# color_Sensor_Schematic.net
KiCad netlist of a schematic drawn in Altium Designer
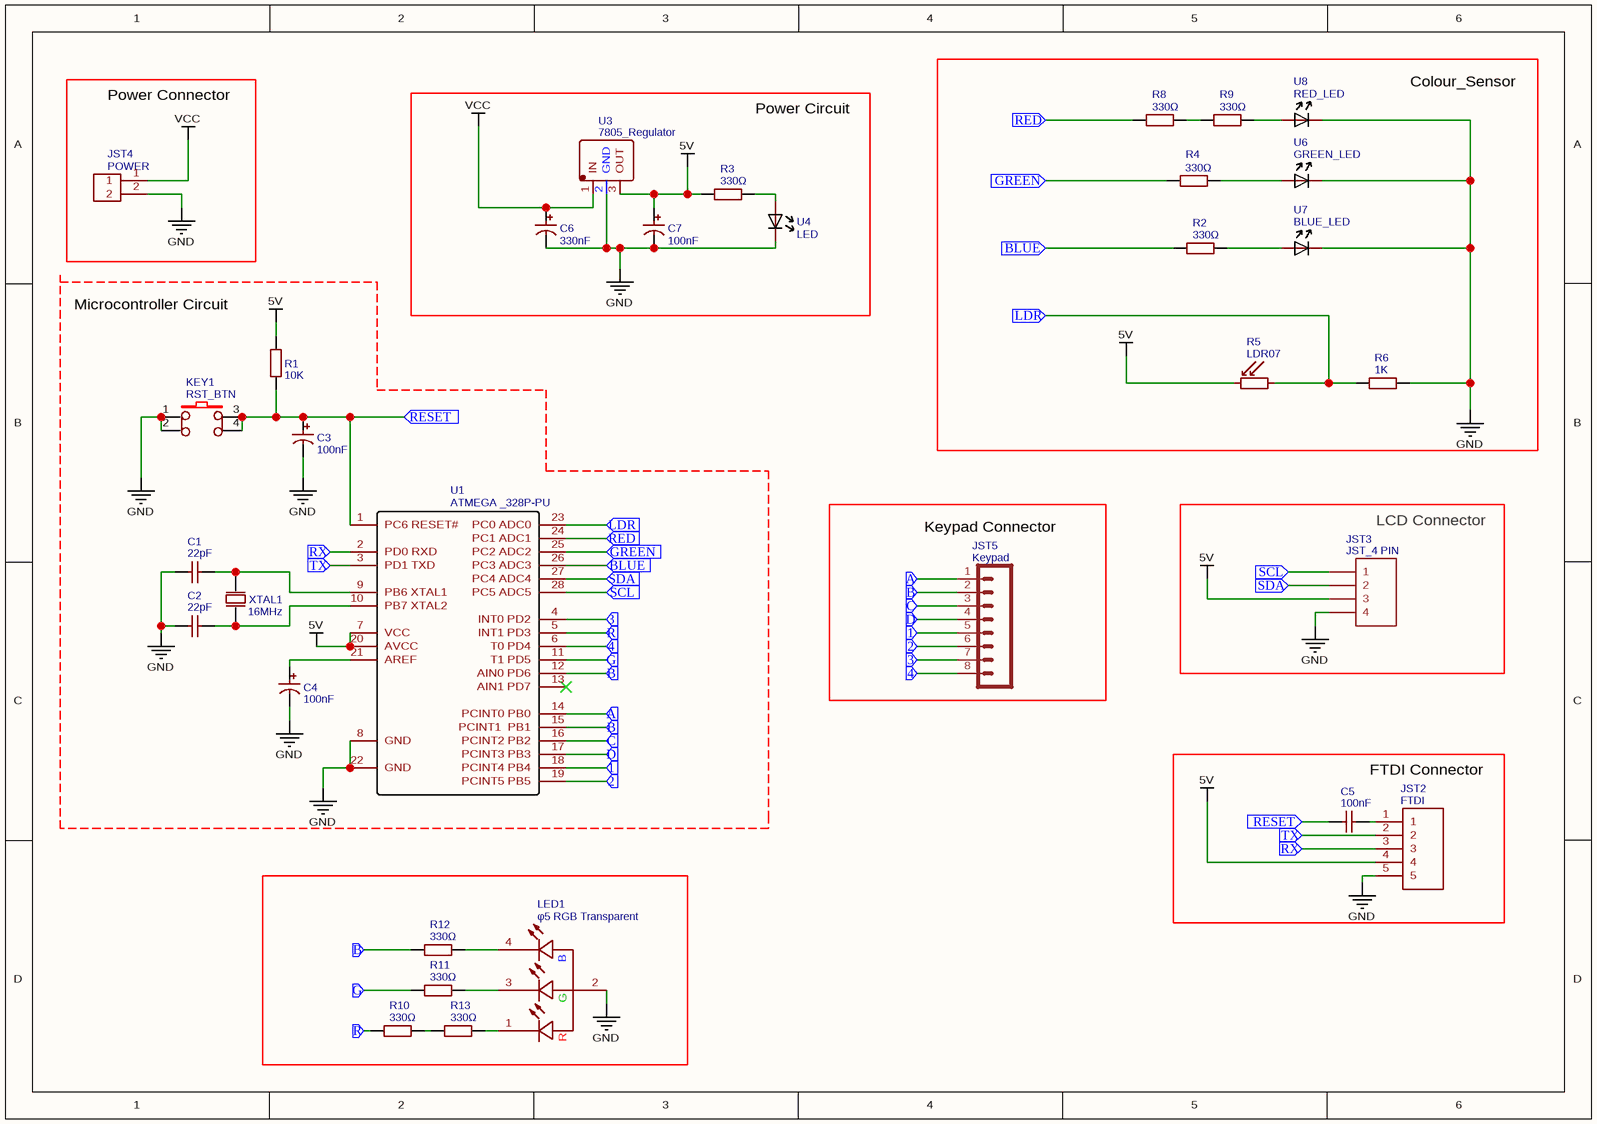
[diagram p0: color Sensor_Schematic.schdoc]

(export (version "E")
  (design (tool "Eeschema 10.0.6"))
  (components
    (comp (ref "C1")
      (value "22pF")
      (fields
        (field (name "BOM_MANUFACTURER PART") "22pf/50V 10%")
        (field (name "BOM_SUPPLIER PART") "C9316")
      )
      (libsource (lib "altium-import") (part "root_0_22pF_"))
    )
    (comp (ref "C2")
      (value "22pF")
      (fields
        (field (name "BOM_MANUFACTURER PART") "22pf/50V 10%")
        (field (name "BOM_SUPPLIER PART") "C9316")
      )
      (libsource (lib "altium-import") (part "root_0_22pF_"))
    )
    (comp (ref "C3")
      (value "100nF")
      (fields (field (name "BOM_MANUFACTURER PART") "0.1UF 50V") (field (name "BOM_SUPPLIER PART") "C28061"))
      (libsource (lib "altium-import") (part "root_0_100nF_"))
    )
    (comp (ref "C4")
      (value "100nF")
      (fields (field (name "BOM_MANUFACTURER PART") "0.1UF 50V") (field (name "BOM_SUPPLIER PART") "C28061"))
      (libsource (lib "altium-import") (part "root_0_100nF_"))
    )
    (comp (ref "C5")
      (value "100nF")
      (fields
        (field (name "BOM_MANUFACTURER PART") "0.1UF(104) +-20% 63v")
        (field (name "BOM_SUPPLIER PART") "C19355")
      )
      (libsource (lib "") (part "root_0_100nF__1"))
    )
    (comp (ref "C6")
      (value "330nF")
      (fields
        (field (name "BOM_MANUFACTURER PART") "0.33uF 50V 5*11")
        (field (name "BOM_SUPPLIER PART") "C45097")
      )
      (libsource (lib "altium-import") (part "root_0_330nF_"))
    )
    (comp (ref "C7")
      (value "100nF")
      (fields (field (name "BOM_MANUFACTURER PART") "0.1UF 50V") (field (name "BOM_SUPPLIER PART") "C28061"))
      (libsource (lib "altium-import") (part "root_0_100nF_"))
    )
    (comp (ref "JST2")
      (value "FTDI")
      (fields (field (name "CONTRIBUTOR") "MagnusInc"))
      (libsource (lib "altium-import") (part "root_3_FTDI_"))
    )
    (comp (ref "JST3")
      (value "JST_4 PIN")
      (fields (field (name "CONTRIBUTOR") "fabiano.riccardi"))
      (libsource (lib "altium-import") (part "root_0_JST_4 PIN_"))
    )
    (comp (ref "JST4")
      (value "POWER")
      (fields
        (field (name "BOM_MANUFACTURER PART") "XHB-2A Connector")
        (field (name "BOM_SUPPLIER PART") "C57981")
      )
      (libsource (lib "altium-import") (part "root_0_POWER_"))
    )
    (comp (ref "JST5")
      (value "Keypad")
      (description "Header 4")
      (fields (field (name "CONTRIBUTOR") "Vlad Tarabega"))
      (libsource (lib "altium-import") (part "root_2_Keypad_"))
    )
    (comp (ref "KEY1")
      (value "RST_BTN")
      (fields
        (field (name "BOM_SUPPLIER PART") "C59980")
        (field (name "BOM_MANUFACTURER PART") "button6*6*8.5")
      )
      (libsource (lib "altium-import") (part "root_0_RST_BTN_"))
    )
    (comp (ref "LED1")
      (value "φ5 RGB Transparent")
      (fields
        (field (name "BOM_MANUFACTURER PART") "φ5 RGB Transparent LED")
        (field (name "BOM_SUPPLIER PART") "C32985")
        (field (name "CONTRIBUTOR") "LCSC")
      )
      (libsource (lib "altium-import") (part "root_3_φ5 RGB Transparent_"))
    )
    (comp (ref "R1")
      (value "10K")
      (fields
        (field (name "POWER") "1/4W")
        (field (name "TOLERANCE") "±1%")
        (field (name "BOM_SUPPLIER PART") "E57439")
      )
      (libsource (lib "altium-import") (part "root_1_10K_"))
    )
    (comp (ref "R2")
      (value "330Ω")
      (fields
        (field (name "POWER") "1/4W")
        (field (name "TOLERANCE") "±1%")
        (field (name "BOM_SUPPLIER PART") "E57439")
      )
      (libsource (lib "altium-import") (part "root_0_330Ω_"))
    )
    (comp (ref "R3")
      (value "330Ω")
      (fields
        (field (name "POWER") "1/4W")
        (field (name "TOLERANCE") "±1%")
        (field (name "BOM_SUPPLIER PART") "E57439")
      )
      (libsource (lib "altium-import") (part "root_0_330Ω_"))
    )
    (comp (ref "R4")
      (value "330Ω")
      (fields
        (field (name "POWER") "1/4W")
        (field (name "TOLERANCE") "±1%")
        (field (name "BOM_SUPPLIER PART") "E57439")
      )
      (libsource (lib "altium-import") (part "root_0_330Ω_"))
    )
    (comp (ref "R5")
      (value "LDR07")
      (fields (field (name "CONTRIBUTOR") "KiCAD"))
      (libsource (lib "altium-import") (part "root_3_LDR07_"))
    )
    (comp (ref "R6")
      (value "1K")
      (fields
        (field (name "POWER") "1/4W")
        (field (name "TOLERANCE") "±1%")
        (field (name "BOM_SUPPLIER PART") "E57439")
      )
      (libsource (lib "altium-import") (part "root_0_1K_"))
    )
    (comp (ref "R8")
      (value "330Ω")
      (fields
        (field (name "POWER") "1/4W")
        (field (name "TOLERANCE") "±1%")
        (field (name "BOM_SUPPLIER PART") "E57439")
      )
      (libsource (lib "altium-import") (part "root_0_330Ω_"))
    )
    (comp (ref "R9")
      (value "330Ω")
      (fields
        (field (name "POWER") "1/4W")
        (field (name "TOLERANCE") "±1%")
        (field (name "BOM_SUPPLIER PART") "E57439")
      )
      (libsource (lib "altium-import") (part "root_0_330Ω_"))
    )
    (comp (ref "R10")
      (value "330Ω")
      (fields
        (field (name "POWER") "1/4W")
        (field (name "TOLERANCE") "±1%")
        (field (name "BOM_SUPPLIER PART") "E57439")
      )
      (libsource (lib "altium-import") (part "root_0_330Ω_"))
    )
    (comp (ref "R11")
      (value "330Ω")
      (fields
        (field (name "POWER") "1/4W")
        (field (name "TOLERANCE") "±1%")
        (field (name "BOM_SUPPLIER PART") "E57439")
      )
      (libsource (lib "altium-import") (part "root_0_330Ω_"))
    )
    (comp (ref "R12")
      (value "330Ω")
      (fields
        (field (name "POWER") "1/4W")
        (field (name "TOLERANCE") "±1%")
        (field (name "BOM_SUPPLIER PART") "E57439")
      )
      (libsource (lib "altium-import") (part "root_0_330Ω_"))
    )
    (comp (ref "R13")
      (value "330Ω")
      (fields
        (field (name "POWER") "1/4W")
        (field (name "TOLERANCE") "±1%")
        (field (name "BOM_SUPPLIER PART") "E57439")
      )
      (libsource (lib "altium-import") (part "root_0_330Ω_"))
    )
    (comp (ref "U1")
      (value "ATMEGA _328P-PU")
      (fields
        (field (name "BOM_MANUFACTURER PART") "ATMEGA328P-PU")
        (field (name "BOM_SUPPLIER PART") "C33901")
        (field (name "CONTRIBUTOR") "LCSC")
      )
      (libsource (lib "altium-import") (part "root_0_ATMEGA _328P-PU_"))
    )
    (comp (ref "U3")
      (value "7805_Regulator")
      (fields
        (field (name "BOM_SUPPLIER PART") "C305416")
        (field (name "BOM_MANUFACTURER PART") "7805")
        (field (name "CONTRIBUTOR") "LCSC")
      )
      (libsource (lib "altium-import") (part "root_1_7805_Regulator_"))
    )
    (comp (ref "U4")
      (value "LED")
      (fields (field (name "BOM_MANUFACTURER PART") "5mm LED") (field (name "CONTRIBUTOR") "Axbri"))
      (libsource (lib "altium-import") (part "root_3_LED_"))
    )
    (comp (ref "U6")
      (value "GREEN_LED")
      (fields (field (name "BOM_MANUFACTURER PART") "5mm LED") (field (name "CONTRIBUTOR") "Axbri"))
      (libsource (lib "altium-import") (part "root_0_GREEN_LED_"))
    )
    (comp (ref "U7")
      (value "BLUE_LED")
      (fields (field (name "BOM_MANUFACTURER PART") "5mm LED") (field (name "CONTRIBUTOR") "Axbri"))
      (libsource (lib "altium-import") (part "root_0_BLUE_LED_"))
    )
    (comp (ref "U8")
      (value "RED_LED")
      (fields (field (name "BOM_MANUFACTURER PART") "5mm LED") (field (name "CONTRIBUTOR") "Axbri"))
      (libsource (lib "altium-import") (part "root_0_RED_LED_"))
    )
    (comp (ref "XTAL1")
      (value "16MHz")
      (fields
        (field (name "BOM_MANUFACTURER PART") "0SC-16MHz")
        (field (name "CONTRIBUTOR") "Mantas Petrauskas")
      )
      (libsource (lib "altium-import") (part "root_1_16MHz_"))
    )
  )
  (nets
    (net (code "1") (name "/1") (class "Default")
      (node (ref "JST5") (pin "5") (pinfunction "5_5") (pintype "passive"))
      (node (ref "U1") (pin "18") (pinfunction "PCINT4_PB4_18") (pintype "passive"))
    )
    (net (code "2") (name "/2") (class "Default")
      (node (ref "JST5") (pin "6") (pinfunction "6_6") (pintype "passive"))
      (node (ref "U1") (pin "19") (pinfunction "PCINT5_PB5_19") (pintype "passive"))
    )
    (net (code "3") (name "/3") (class "Default")
      (node (ref "JST5") (pin "7") (pinfunction "7_7") (pintype "passive"))
      (node (ref "U1") (pin "4") (pinfunction "INT0_PD2_4") (pintype "passive"))
    )
    (net (code "4") (name "/4") (class "Default")
      (node (ref "JST5") (pin "8") (pinfunction "8_8") (pintype "passive"))
      (node (ref "U1") (pin "6") (pinfunction "T0_PD4_6") (pintype "passive"))
    )
    (net (code "5") (name "/A") (class "Default")
      (node (ref "JST5") (pin "1") (pinfunction "1_1") (pintype "passive"))
      (node (ref "U1") (pin "14") (pinfunction "PCINT0_PB0_14") (pintype "passive"))
    )
    (net (code "6") (name "/B") (class "Default")
      (node (ref "JST5") (pin "2") (pinfunction "2_2") (pintype "passive"))
      (node (ref "R12") (pin "1") (pinfunction "1_1") (pintype "passive"))
      (node (ref "U1") (pin "12") (pinfunction "AIN0_PD6_12") (pintype "passive"))
      (node (ref "U1") (pin "15") (pinfunction "PCINT1__PB1_15") (pintype "passive"))
    )
    (net (code "7") (name "/BLUE") (class "Default")
      (node (ref "R2") (pin "1") (pinfunction "1_1") (pintype "passive"))
      (node (ref "U1") (pin "26") (pinfunction "PC3_ADC3_26") (pintype "passive"))
    )
    (net (code "8") (name "/C") (class "Default")
      (node (ref "JST5") (pin "3") (pinfunction "3_3") (pintype "passive"))
      (node (ref "U1") (pin "16") (pinfunction "PCINT2_PB2_16") (pintype "passive"))
    )
    (net (code "9") (name "/D") (class "Default")
      (node (ref "JST5") (pin "4") (pinfunction "4_4") (pintype "passive"))
      (node (ref "U1") (pin "17") (pinfunction "PCINT3_PB3_17") (pintype "passive"))
    )
    (net (code "10") (name "/G") (class "Default")
      (node (ref "R11") (pin "1") (pinfunction "1_1") (pintype "passive"))
      (node (ref "U1") (pin "11") (pinfunction "T1_PD5_11") (pintype "passive"))
    )
    (net (code "11") (name "/GREEN") (class "Default")
      (node (ref "R4") (pin "1") (pinfunction "1_1") (pintype "passive"))
      (node (ref "U1") (pin "25") (pinfunction "PC2_ADC2_25") (pintype "passive"))
    )
    (net (code "12") (name "/LDR") (class "Default")
      (node (ref "R5") (pin "1") (pintype "passive"))
      (node (ref "R6") (pin "1") (pinfunction "1_1") (pintype "passive"))
      (node (ref "U1") (pin "23") (pinfunction "PC0_ADC0_23") (pintype "passive"))
    )
    (net (code "13") (name "/R") (class "Default")
      (node (ref "R10") (pin "1") (pinfunction "1_1") (pintype "passive"))
      (node (ref "U1") (pin "5") (pinfunction "INT1_PD3_5") (pintype "passive"))
    )
    (net (code "14") (name "/RED") (class "Default")
      (node (ref "R8") (pin "1") (pinfunction "1_1") (pintype "passive"))
      (node (ref "U1") (pin "24") (pinfunction "PC1_ADC1_24") (pintype "passive"))
    )
    (net (code "15") (name "/RESET") (class "Default")
      (node (ref "C3") (pin "1") (pinfunction "1_1") (pintype "passive"))
      (node (ref "C5") (pin "1") (pinfunction "1_1") (pintype "passive"))
      (node (ref "KEY1") (pin "3") (pinfunction "3_3") (pintype "passive"))
      (node (ref "KEY1") (pin "4") (pinfunction "4_4") (pintype "passive"))
      (node (ref "R1") (pin "1") (pinfunction "1_1") (pintype "passive"))
      (node (ref "U1") (pin "1") (pinfunction "PC6_RESET#_1") (pintype "passive"))
    )
    (net (code "16") (name "/RX") (class "Default")
      (node (ref "JST2") (pin "3") (pinfunction "3_3") (pintype "passive"))
      (node (ref "U1") (pin "2") (pinfunction "PD0_RXD_2") (pintype "passive"))
    )
    (net (code "17") (name "/SCL") (class "Default")
      (node (ref "JST3") (pin "1") (pinfunction "1_1") (pintype "passive"))
      (node (ref "U1") (pin "28") (pinfunction "PC5_ADC5_28") (pintype "passive"))
    )
    (net (code "18") (name "/SDA") (class "Default")
      (node (ref "JST3") (pin "2") (pinfunction "2_2") (pintype "passive"))
      (node (ref "U1") (pin "27") (pinfunction "PC4_ADC4_27") (pintype "passive"))
    )
    (net (code "19") (name "/TX") (class "Default")
      (node (ref "JST2") (pin "2") (pinfunction "2_2") (pintype "passive"))
      (node (ref "U1") (pin "3") (pinfunction "PD1_TXD_3") (pintype "passive"))
    )
    (net (code "20") (name "5V") (class "Default")
      (node (ref "C7") (pin "1") (pinfunction "1_1") (pintype "passive"))
      (node (ref "JST2") (pin "4") (pinfunction "4_4") (pintype "passive"))
      (node (ref "JST3") (pin "3") (pinfunction "3_3") (pintype "passive"))
      (node (ref "R1") (pin "2") (pinfunction "2_2") (pintype "passive"))
      (node (ref "R3") (pin "1") (pinfunction "1_1") (pintype "passive"))
      (node (ref "R5") (pin "2") (pintype "passive"))
      (node (ref "U1") (pin "20") (pinfunction "AVCC_20") (pintype "passive"))
      (node (ref "U1") (pin "7") (pinfunction "VCC_7") (pintype "passive"))
      (node (ref "U3") (pin "3") (pinfunction "OUT_3") (pintype "passive"))
    )
    (net (code "21") (name "GND") (class "Default")
      (node (ref "C1") (pin "1") (pinfunction "1_1") (pintype "passive"))
      (node (ref "C2") (pin "1") (pinfunction "1_1") (pintype "passive"))
      (node (ref "C3") (pin "2") (pinfunction "2_2") (pintype "passive"))
      (node (ref "C4") (pin "2") (pinfunction "2_2") (pintype "passive"))
      (node (ref "C6") (pin "2") (pinfunction "2_2") (pintype "passive"))
      (node (ref "C7") (pin "2") (pinfunction "2_2") (pintype "passive"))
      (node (ref "JST2") (pin "5") (pinfunction "5_5") (pintype "passive"))
      (node (ref "JST3") (pin "4") (pinfunction "4_4") (pintype "passive"))
      (node (ref "JST4") (pin "2") (pinfunction "2_2") (pintype "passive"))
      (node (ref "KEY1") (pin "1") (pinfunction "1_1") (pintype "passive"))
      (node (ref "KEY1") (pin "2") (pinfunction "2_2") (pintype "passive"))
      (node (ref "LED1") (pin "2") (pinfunction "CA_2") (pintype "passive"))
      (node (ref "R6") (pin "2") (pinfunction "2_2") (pintype "passive"))
      (node (ref "U1") (pin "22") (pinfunction "GND_22") (pintype "passive"))
      (node (ref "U1") (pin "8") (pinfunction "GND_8") (pintype "passive"))
      (node (ref "U3") (pin "2") (pinfunction "GND_2") (pintype "passive"))
      (node (ref "U4") (pin "2") (pinfunction "2_2") (pintype "passive"))
      (node (ref "U6") (pin "2") (pinfunction "2_2") (pintype "passive"))
      (node (ref "U7") (pin "2") (pinfunction "2_2") (pintype "passive"))
      (node (ref "U8") (pin "2") (pinfunction "2_2") (pintype "passive"))
    )
    (net (code "22") (name "Net-(C5-Pad2)") (class "Default")
      (node (ref "C5") (pin "2") (pinfunction "2_2") (pintype "passive"))
      (node (ref "JST2") (pin "1") (pinfunction "1_1") (pintype "passive"))
    )
    (net (code "23") (name "Net-(LED1-KB)") (class "Default")
      (node (ref "LED1") (pin "4") (pinfunction "KB_4") (pintype "passive"))
      (node (ref "R12") (pin "2") (pinfunction "2_2") (pintype "passive"))
    )
    (net (code "24") (name "Net-(LED1-KG)") (class "Default")
      (node (ref "LED1") (pin "3") (pinfunction "KG_3") (pintype "passive"))
      (node (ref "R11") (pin "2") (pinfunction "2_2") (pintype "passive"))
    )
    (net (code "25") (name "Net-(LED1-KR)") (class "Default")
      (node (ref "LED1") (pin "1") (pinfunction "KR_1") (pintype "passive"))
      (node (ref "R13") (pin "2") (pinfunction "2_2") (pintype "passive"))
    )
    (net (code "26") (name "Net-(R2-Pad2)") (class "Default")
      (node (ref "R2") (pin "2") (pinfunction "2_2") (pintype "passive"))
      (node (ref "U7") (pin "1") (pinfunction "1_1") (pintype "passive"))
    )
    (net (code "27") (name "Net-(R3-Pad2)") (class "Default")
      (node (ref "R3") (pin "2") (pinfunction "2_2") (pintype "passive"))
      (node (ref "U4") (pin "1") (pinfunction "1_1") (pintype "passive"))
    )
    (net (code "28") (name "Net-(R4-Pad2)") (class "Default")
      (node (ref "R4") (pin "2") (pinfunction "2_2") (pintype "passive"))
      (node (ref "U6") (pin "1") (pinfunction "1_1") (pintype "passive"))
    )
    (net (code "29") (name "Net-(R8-Pad2)") (class "Default")
      (node (ref "R8") (pin "2") (pinfunction "2_2") (pintype "passive"))
      (node (ref "R9") (pin "1") (pinfunction "1_1") (pintype "passive"))
    )
    (net (code "30") (name "Net-(R9-Pad2)") (class "Default")
      (node (ref "R9") (pin "2") (pinfunction "2_2") (pintype "passive"))
      (node (ref "U8") (pin "1") (pinfunction "1_1") (pintype "passive"))
    )
    (net (code "31") (name "Net-(R10-Pad2)") (class "Default")
      (node (ref "R10") (pin "2") (pinfunction "2_2") (pintype "passive"))
      (node (ref "R13") (pin "1") (pinfunction "1_1") (pintype "passive"))
    )
    (net (code "32") (name "Net-(U1-AREF)") (class "Default")
      (node (ref "C4") (pin "1") (pinfunction "1_1") (pintype "passive"))
      (node (ref "U1") (pin "21") (pinfunction "AREF_21") (pintype "passive"))
    )
    (net (code "33") (name "Net-(U1-PB6_XTAL1)") (class "Default")
      (node (ref "C1") (pin "2") (pinfunction "2_2") (pintype "passive"))
      (node (ref "U1") (pin "9") (pinfunction "PB6_XTAL1_9") (pintype "passive"))
      (node (ref "XTAL1") (pin "1") (pinfunction "OSC1_1") (pintype "passive"))
    )
    (net (code "34") (name "Net-(U1-PB7_XTAL2)") (class "Default")
      (node (ref "C2") (pin "2") (pinfunction "2_2") (pintype "passive"))
      (node (ref "U1") (pin "10") (pinfunction "PB7_XTAL2_10") (pintype "passive"))
      (node (ref "XTAL1") (pin "2") (pinfunction "OSC2_2") (pintype "passive"))
    )
    (net (code "35") (name "VCC") (class "Default")
      (node (ref "C6") (pin "1") (pinfunction "1_1") (pintype "passive"))
      (node (ref "JST4") (pin "1") (pinfunction "1_1") (pintype "passive"))
      (node (ref "U3") (pin "1") (pinfunction "IN_1") (pintype "passive"))
    )
    (net (code "36") (name "unconnected-(U1-AIN1_PD7-Pad13)") (class "Default")
      (node (ref "U1") (pin "13") (pinfunction "AIN1_PD7_13") (pintype "passive+no_connect"))
    )
  )
)
